# microcontroller_r1.net
KiCad netlist of a schematic drawn in EAGLE
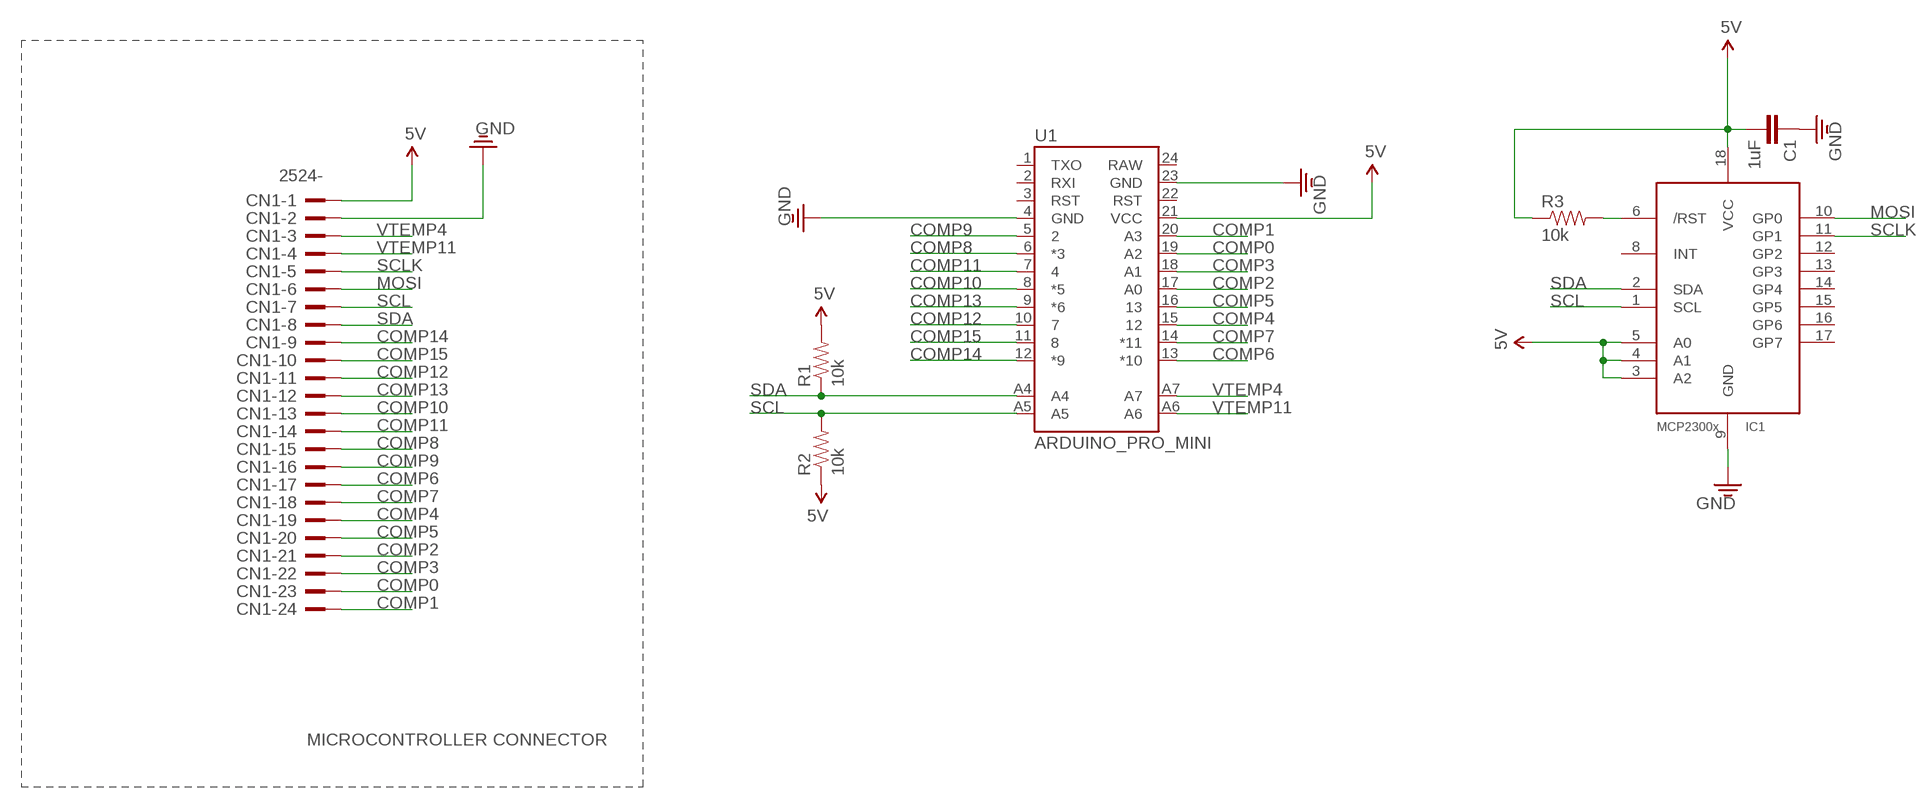
[diagram p0: schematic, sheet 1]

(export (version "E")
  (design (tool "Eeschema 10.0.6"))
  (components
    (comp (ref "C1")
      (value "1uF")
      (footprint "eagle-import:0603")
      (libsource (lib "eagle-import") (part "CAP0603"))
    )
    (comp (ref "CN1")
      (value "2524-")
      (footprint "eagle-import:PAK100_2500-24")
      (libsource (lib "eagle-import") (part "2524-"))
    )
    (comp (ref "IC1")
      (value "MCP2300X/SO")
      (footprint "eagle-import:SO18W")
      (libsource (lib "eagle-import") (part "MCP2300X/SO"))
    )
    (comp (ref "R1")
      (value "10k")
      (footprint "eagle-import:0603")
      (libsource (lib "eagle-import") (part "RESISTOR0603"))
    )
    (comp (ref "R2")
      (value "10k")
      (footprint "eagle-import:0603")
      (libsource (lib "eagle-import") (part "RESISTOR0603"))
    )
    (comp (ref "R3")
      (value "10k")
      (footprint "eagle-import:0603")
      (libsource (lib "eagle-import") (part "RESISTOR0603"))
    )
    (comp (ref "U1")
      (value "ARDUINO_PRO_MINI")
      (footprint "eagle-import:ARDUINO_PRO_MINI")
      (libsource (lib "eagle-import") (part "ARDUINO_PRO_MINI"))
    )
  )
  (nets
    (net (code "1") (name "/COMP0") (class "Default")
      (node (ref "CN1") (pin "23") (pinfunction "KL_23") (pintype "passive"))
      (node (ref "U1") (pin "19") (pinfunction "A2_19") (pintype "bidirectional"))
    )
    (net (code "2") (name "/COMP1") (class "Default")
      (node (ref "CN1") (pin "24") (pinfunction "KL_24") (pintype "passive"))
      (node (ref "U1") (pin "20") (pinfunction "A3_20") (pintype "bidirectional"))
    )
    (net (code "3") (name "/COMP2") (class "Default")
      (node (ref "CN1") (pin "21") (pinfunction "KL_21") (pintype "passive"))
      (node (ref "U1") (pin "17") (pinfunction "A0_17") (pintype "bidirectional"))
    )
    (net (code "4") (name "/COMP3") (class "Default")
      (node (ref "CN1") (pin "22") (pinfunction "KL_22") (pintype "passive"))
      (node (ref "U1") (pin "18") (pinfunction "A1_18") (pintype "bidirectional"))
    )
    (net (code "5") (name "/COMP4") (class "Default")
      (node (ref "CN1") (pin "19") (pinfunction "KL_19") (pintype "passive"))
      (node (ref "U1") (pin "15") (pinfunction "12_15") (pintype "bidirectional"))
    )
    (net (code "6") (name "/COMP5") (class "Default")
      (node (ref "CN1") (pin "20") (pinfunction "KL_20") (pintype "passive"))
      (node (ref "U1") (pin "16") (pinfunction "13_16") (pintype "bidirectional"))
    )
    (net (code "7") (name "/COMP6") (class "Default")
      (node (ref "CN1") (pin "17") (pinfunction "KL_17") (pintype "passive"))
      (node (ref "U1") (pin "13") (pinfunction "*10_13") (pintype "bidirectional"))
    )
    (net (code "8") (name "/COMP7") (class "Default")
      (node (ref "CN1") (pin "18") (pinfunction "KL_18") (pintype "passive"))
      (node (ref "U1") (pin "14") (pinfunction "*11_14") (pintype "bidirectional"))
    )
    (net (code "9") (name "/COMP8") (class "Default")
      (node (ref "CN1") (pin "15") (pinfunction "KL_15") (pintype "passive"))
      (node (ref "U1") (pin "6") (pinfunction "*3_6") (pintype "bidirectional"))
    )
    (net (code "10") (name "/COMP9") (class "Default")
      (node (ref "CN1") (pin "16") (pinfunction "KL_16") (pintype "passive"))
      (node (ref "U1") (pin "5") (pinfunction "2_5") (pintype "bidirectional"))
    )
    (net (code "11") (name "/COMP10") (class "Default")
      (node (ref "CN1") (pin "13") (pinfunction "KL_13") (pintype "passive"))
      (node (ref "U1") (pin "8") (pinfunction "*5_8") (pintype "bidirectional"))
    )
    (net (code "12") (name "/COMP11") (class "Default")
      (node (ref "CN1") (pin "14") (pinfunction "KL_14") (pintype "passive"))
      (node (ref "U1") (pin "7") (pinfunction "4_7") (pintype "bidirectional"))
    )
    (net (code "13") (name "/COMP12") (class "Default")
      (node (ref "CN1") (pin "11") (pinfunction "KL_11") (pintype "passive"))
      (node (ref "U1") (pin "10") (pinfunction "7_10") (pintype "bidirectional"))
    )
    (net (code "14") (name "/COMP13") (class "Default")
      (node (ref "CN1") (pin "12") (pinfunction "KL_12") (pintype "passive"))
      (node (ref "U1") (pin "9") (pinfunction "*6_9") (pintype "bidirectional"))
    )
    (net (code "15") (name "/COMP14") (class "Default")
      (node (ref "CN1") (pin "9") (pinfunction "KL_9") (pintype "passive"))
      (node (ref "U1") (pin "12") (pinfunction "*9_12") (pintype "bidirectional"))
    )
    (net (code "16") (name "/COMP15") (class "Default")
      (node (ref "CN1") (pin "10") (pinfunction "KL_10") (pintype "passive"))
      (node (ref "U1") (pin "11") (pinfunction "8_11") (pintype "bidirectional"))
    )
    (net (code "17") (name "/MOSI") (class "Default")
      (node (ref "CN1") (pin "6") (pinfunction "KL_6") (pintype "passive"))
      (node (ref "IC1") (pin "10") (pinfunction "GP0_10") (pintype "bidirectional"))
    )
    (net (code "18") (name "/SCL") (class "Default")
      (node (ref "CN1") (pin "7") (pinfunction "KL_7") (pintype "passive"))
      (node (ref "IC1") (pin "1") (pinfunction "SCL_1") (pintype "bidirectional"))
      (node (ref "R2") (pin "2") (pinfunction "2_2") (pintype "passive"))
      (node (ref "U1") (pin "A5") (pinfunction "A5_A5") (pintype "bidirectional"))
    )
    (net (code "19") (name "/SCLK") (class "Default")
      (node (ref "CN1") (pin "5") (pinfunction "KL_5") (pintype "passive"))
      (node (ref "IC1") (pin "11") (pinfunction "GP1_11") (pintype "bidirectional"))
    )
    (net (code "20") (name "/SDA") (class "Default")
      (node (ref "CN1") (pin "8") (pinfunction "KL_8") (pintype "passive"))
      (node (ref "IC1") (pin "2") (pinfunction "SDA_2") (pintype "bidirectional"))
      (node (ref "R1") (pin "1") (pinfunction "1_1") (pintype "passive"))
      (node (ref "U1") (pin "A4") (pinfunction "A4_A4") (pintype "bidirectional"))
    )
    (net (code "21") (name "/VTEMP4") (class "Default")
      (node (ref "CN1") (pin "3") (pinfunction "KL_3") (pintype "passive"))
      (node (ref "U1") (pin "A7") (pinfunction "A7_A7") (pintype "bidirectional"))
    )
    (net (code "22") (name "/VTEMP11") (class "Default")
      (node (ref "CN1") (pin "4") (pinfunction "KL_4") (pintype "passive"))
      (node (ref "U1") (pin "A6") (pinfunction "A6_A6") (pintype "bidirectional"))
    )
    (net (code "23") (name "5V") (class "Default")
      (node (ref "C1") (pin "2") (pinfunction "2_2") (pintype "passive"))
      (node (ref "CN1") (pin "1") (pinfunction "KL_1") (pintype "passive"))
      (node (ref "IC1") (pin "18") (pinfunction "VCC_18") (pintype "power_in"))
      (node (ref "IC1") (pin "3") (pinfunction "A2_3") (pintype "input"))
      (node (ref "IC1") (pin "4") (pinfunction "A1_4") (pintype "input"))
      (node (ref "IC1") (pin "5") (pinfunction "A0_5") (pintype "input"))
      (node (ref "R1") (pin "2") (pinfunction "2_2") (pintype "passive"))
      (node (ref "R2") (pin "1") (pinfunction "1_1") (pintype "passive"))
      (node (ref "R3") (pin "1") (pinfunction "1_1") (pintype "passive"))
      (node (ref "U1") (pin "21") (pinfunction "VCC_21") (pintype "bidirectional"))
    )
    (net (code "24") (name "GND") (class "Default")
      (node (ref "C1") (pin "1") (pinfunction "1_1") (pintype "passive"))
      (node (ref "CN1") (pin "2") (pinfunction "KL_2") (pintype "passive"))
      (node (ref "IC1") (pin "9") (pinfunction "GND_9") (pintype "power_in"))
      (node (ref "U1") (pin "23") (pinfunction "GND_23") (pintype "bidirectional"))
      (node (ref "U1") (pin "4") (pinfunction "GND_4") (pintype "bidirectional"))
    )
    (net (code "25") (name "Net-(IC1-{slash}RST)") (class "Default")
      (node (ref "IC1") (pin "6") (pinfunction "/RST_6") (pintype "input"))
      (node (ref "R3") (pin "2") (pinfunction "2_2") (pintype "passive"))
    )
    (net (code "26") (name "unconnected-(IC1-GP2-Pad12)") (class "Default")
      (node (ref "IC1") (pin "12") (pinfunction "GP2_12") (pintype "bidirectional"))
    )
    (net (code "27") (name "unconnected-(IC1-GP3-Pad13)") (class "Default")
      (node (ref "IC1") (pin "13") (pinfunction "GP3_13") (pintype "bidirectional"))
    )
    (net (code "28") (name "unconnected-(IC1-GP4-Pad14)") (class "Default")
      (node (ref "IC1") (pin "14") (pinfunction "GP4_14") (pintype "bidirectional"))
    )
    (net (code "29") (name "unconnected-(IC1-GP5-Pad15)") (class "Default")
      (node (ref "IC1") (pin "15") (pinfunction "GP5_15") (pintype "bidirectional"))
    )
    (net (code "30") (name "unconnected-(IC1-GP6-Pad16)") (class "Default")
      (node (ref "IC1") (pin "16") (pinfunction "GP6_16") (pintype "bidirectional"))
    )
    (net (code "31") (name "unconnected-(IC1-GP7-Pad17)") (class "Default")
      (node (ref "IC1") (pin "17") (pinfunction "GP7_17") (pintype "bidirectional"))
    )
    (net (code "32") (name "unconnected-(IC1-INT-Pad8)") (class "Default")
      (node (ref "IC1") (pin "8") (pinfunction "INT_8") (pintype "output"))
    )
    (net (code "33") (name "unconnected-(U1-RAW-Pad24)") (class "Default")
      (node (ref "U1") (pin "24") (pinfunction "RAW_24") (pintype "bidirectional"))
    )
    (net (code "34") (name "unconnected-(U1-RST-Pad3)") (class "Default")
      (node (ref "U1") (pin "3") (pinfunction "RST_3") (pintype "bidirectional"))
    )
    (net (code "35") (name "unconnected-(U1-RST-Pad22)") (class "Default")
      (node (ref "U1") (pin "22") (pinfunction "RST_22") (pintype "bidirectional"))
    )
    (net (code "36") (name "unconnected-(U1-RXI-Pad2)") (class "Default")
      (node (ref "U1") (pin "2") (pinfunction "RXI_2") (pintype "bidirectional"))
    )
    (net (code "37") (name "unconnected-(U1-TXO-Pad1)") (class "Default")
      (node (ref "U1") (pin "1") (pinfunction "TXO_1") (pintype "bidirectional"))
    )
  )
)
